# ResDivider.net
KiCad netlist of a schematic drawn in Altium Designer
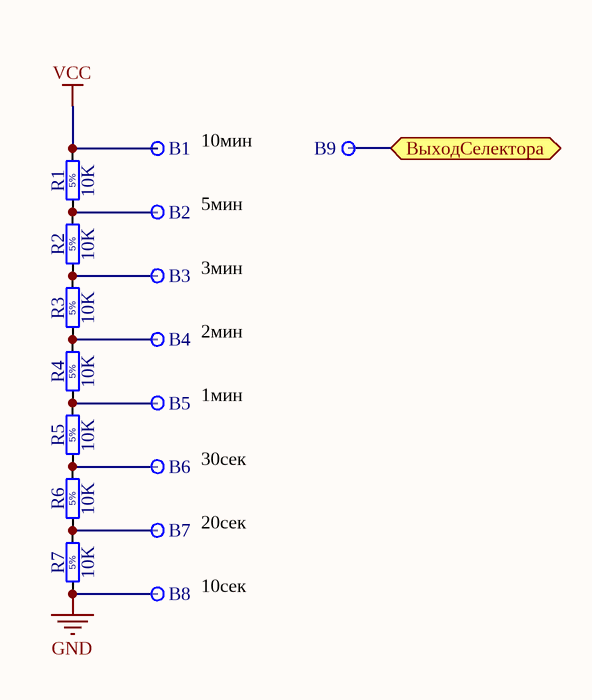
[diagram p0: ResDivider.SchDoc]

(export (version "E")
  (design (tool "Eeschema 10.0.6"))
  (components
    (comp (ref "B1")
      (value "Plated Hole")
      (footprint "c180h130")
      (description "Single Terminal Socket")
      (fields (field (name "PART NUMBER") "PLATED_HOLE1.3_PAD1.8") (field (name "AUTHOR") "CERN DEM JLC"))
      (libsource (lib "Eletro-mechanical") (part "Single Terminal Socket"))
    )
    (comp (ref "B2")
      (value "Plated Hole")
      (footprint "c180h130")
      (description "Single Terminal Socket")
      (fields (field (name "PART NUMBER") "PLATED_HOLE1.3_PAD1.8") (field (name "AUTHOR") "CERN DEM JLC"))
      (libsource (lib "Eletro-mechanical") (part "Single Terminal Socket"))
    )
    (comp (ref "B3")
      (value "Plated Hole")
      (footprint "c180h130")
      (description "Single Terminal Socket")
      (fields (field (name "PART NUMBER") "PLATED_HOLE1.3_PAD1.8") (field (name "AUTHOR") "CERN DEM JLC"))
      (libsource (lib "Eletro-mechanical") (part "Single Terminal Socket"))
    )
    (comp (ref "B4")
      (value "Plated Hole")
      (footprint "c180h130")
      (description "Single Terminal Socket")
      (fields (field (name "PART NUMBER") "PLATED_HOLE1.3_PAD1.8") (field (name "AUTHOR") "CERN DEM JLC"))
      (libsource (lib "Eletro-mechanical") (part "Single Terminal Socket"))
    )
    (comp (ref "B5")
      (value "Plated Hole")
      (footprint "c180h130")
      (description "Single Terminal Socket")
      (fields (field (name "PART NUMBER") "PLATED_HOLE1.3_PAD1.8") (field (name "AUTHOR") "CERN DEM JLC"))
      (libsource (lib "Eletro-mechanical") (part "Single Terminal Socket"))
    )
    (comp (ref "B6")
      (value "Plated Hole")
      (footprint "c180h130")
      (description "Single Terminal Socket")
      (fields (field (name "PART NUMBER") "PLATED_HOLE1.3_PAD1.8") (field (name "AUTHOR") "CERN DEM JLC"))
      (libsource (lib "Eletro-mechanical") (part "Single Terminal Socket"))
    )
    (comp (ref "B7")
      (value "Plated Hole")
      (footprint "c180h130")
      (description "Single Terminal Socket")
      (fields (field (name "PART NUMBER") "PLATED_HOLE1.3_PAD1.8") (field (name "AUTHOR") "CERN DEM JLC"))
      (libsource (lib "Eletro-mechanical") (part "Single Terminal Socket"))
    )
    (comp (ref "B8")
      (value "Plated Hole")
      (footprint "c180h130")
      (description "Single Terminal Socket")
      (fields (field (name "PART NUMBER") "PLATED_HOLE1.3_PAD1.8") (field (name "AUTHOR") "CERN DEM JLC"))
      (libsource (lib "Eletro-mechanical") (part "Single Terminal Socket"))
    )
    (comp (ref "B9")
      (value "Plated Hole")
      (footprint "c180h130")
      (description "Single Terminal Socket")
      (fields (field (name "PART NUMBER") "PLATED_HOLE1.3_PAD1.8") (field (name "AUTHOR") "CERN DEM JLC"))
      (libsource (lib "Eletro-mechanical") (part "Single Terminal Socket"))
    )
    (comp (ref "R1")
      (value "10K")
      (footprint "RES_ARCOL_RCC025")
      (description "Resistor - 5%")
      (fields
        (field (name "PART NUMBER") "RCF_5K1_5%_0.25W_+10-6PPM_ARCOL_RCC025")
        (field (name "POWER") "0.25W")
        (field (name "AUTHOR") "CERN DEM JLC")
      )
      (libsource (lib "Resistors") (part "Resistor - 5%"))
    )
    (comp (ref "R2")
      (value "10K")
      (footprint "RES_ARCOL_RCC025")
      (description "Resistor - 5%")
      (fields
        (field (name "PART NUMBER") "RCF_5K1_5%_0.25W_+10-6PPM_ARCOL_RCC025")
        (field (name "POWER") "0.25W")
        (field (name "AUTHOR") "CERN DEM JLC")
      )
      (libsource (lib "Resistors") (part "Resistor - 5%"))
    )
    (comp (ref "R3")
      (value "10K")
      (footprint "RES_ARCOL_RCC025")
      (description "Resistor - 5%")
      (fields
        (field (name "PART NUMBER") "RCF_5K1_5%_0.25W_+10-6PPM_ARCOL_RCC025")
        (field (name "POWER") "0.25W")
        (field (name "AUTHOR") "CERN DEM JLC")
      )
      (libsource (lib "Resistors") (part "Resistor - 5%"))
    )
    (comp (ref "R4")
      (value "10K")
      (footprint "RES_ARCOL_RCC025")
      (description "Resistor - 5%")
      (fields
        (field (name "PART NUMBER") "RCF_5K1_5%_0.25W_+10-6PPM_ARCOL_RCC025")
        (field (name "POWER") "0.25W")
        (field (name "AUTHOR") "CERN DEM JLC")
      )
      (libsource (lib "Resistors") (part "Resistor - 5%"))
    )
    (comp (ref "R5")
      (value "10K")
      (footprint "RES_ARCOL_RCC025")
      (description "Resistor - 5%")
      (fields
        (field (name "PART NUMBER") "RCF_5K1_5%_0.25W_+10-6PPM_ARCOL_RCC025")
        (field (name "POWER") "0.25W")
        (field (name "AUTHOR") "CERN DEM JLC")
      )
      (libsource (lib "Resistors") (part "Resistor - 5%"))
    )
    (comp (ref "R6")
      (value "10K")
      (footprint "RES_ARCOL_RCC025")
      (description "Resistor - 5%")
      (fields
        (field (name "PART NUMBER") "RCF_5K1_5%_0.25W_+10-6PPM_ARCOL_RCC025")
        (field (name "POWER") "0.25W")
        (field (name "AUTHOR") "CERN DEM JLC")
      )
      (libsource (lib "Resistors") (part "Resistor - 5%"))
    )
    (comp (ref "R7")
      (value "10K")
      (footprint "RES_ARCOL_RCC025")
      (description "Resistor - 5%")
      (fields
        (field (name "PART NUMBER") "RCF_5K1_5%_0.25W_+10-6PPM_ARCOL_RCC025")
        (field (name "POWER") "0.25W")
        (field (name "AUTHOR") "CERN DEM JLC")
      )
      (libsource (lib "Resistors") (part "Resistor - 5%"))
    )
  )
  (nets
    (net (code "1") (name "/ВыходСелектора") (class "Default")
      (node (ref "B9") (pin "1") (pinfunction "1_1") (pintype "bidirectional"))
    )
    (net (code "2") (name "GND") (class "Default")
      (node (ref "B8") (pin "1") (pinfunction "1_1") (pintype "bidirectional"))
      (node (ref "R7") (pin "1") (pinfunction "1_1") (pintype "passive"))
    )
    (net (code "3") (name "Net-(B2-Pad1)") (class "Default")
      (node (ref "B2") (pin "1") (pinfunction "1_1") (pintype "bidirectional"))
      (node (ref "R1") (pin "1") (pinfunction "1_1") (pintype "passive"))
      (node (ref "R2") (pin "2") (pinfunction "2_2") (pintype "passive"))
    )
    (net (code "4") (name "Net-(B3-Pad1)") (class "Default")
      (node (ref "B3") (pin "1") (pinfunction "1_1") (pintype "bidirectional"))
      (node (ref "R2") (pin "1") (pinfunction "1_1") (pintype "passive"))
      (node (ref "R3") (pin "2") (pinfunction "2_2") (pintype "passive"))
    )
    (net (code "5") (name "Net-(B4-Pad1)") (class "Default")
      (node (ref "B4") (pin "1") (pinfunction "1_1") (pintype "bidirectional"))
      (node (ref "R3") (pin "1") (pinfunction "1_1") (pintype "passive"))
      (node (ref "R4") (pin "2") (pinfunction "2_2") (pintype "passive"))
    )
    (net (code "6") (name "Net-(B5-Pad1)") (class "Default")
      (node (ref "B5") (pin "1") (pinfunction "1_1") (pintype "bidirectional"))
      (node (ref "R4") (pin "1") (pinfunction "1_1") (pintype "passive"))
      (node (ref "R5") (pin "2") (pinfunction "2_2") (pintype "passive"))
    )
    (net (code "7") (name "Net-(B6-Pad1)") (class "Default")
      (node (ref "B6") (pin "1") (pinfunction "1_1") (pintype "bidirectional"))
      (node (ref "R5") (pin "1") (pinfunction "1_1") (pintype "passive"))
      (node (ref "R6") (pin "2") (pinfunction "2_2") (pintype "passive"))
    )
    (net (code "8") (name "Net-(B7-Pad1)") (class "Default")
      (node (ref "B7") (pin "1") (pinfunction "1_1") (pintype "bidirectional"))
      (node (ref "R6") (pin "1") (pinfunction "1_1") (pintype "passive"))
      (node (ref "R7") (pin "2") (pinfunction "2_2") (pintype "passive"))
    )
    (net (code "9") (name "VCC") (class "Default")
      (node (ref "B1") (pin "1") (pinfunction "1_1") (pintype "bidirectional"))
      (node (ref "R1") (pin "2") (pinfunction "2_2") (pintype "passive"))
    )
  )
)
